# SparkFun_NEO-F9P.net
KiCad netlist of a schematic drawn in EAGLE
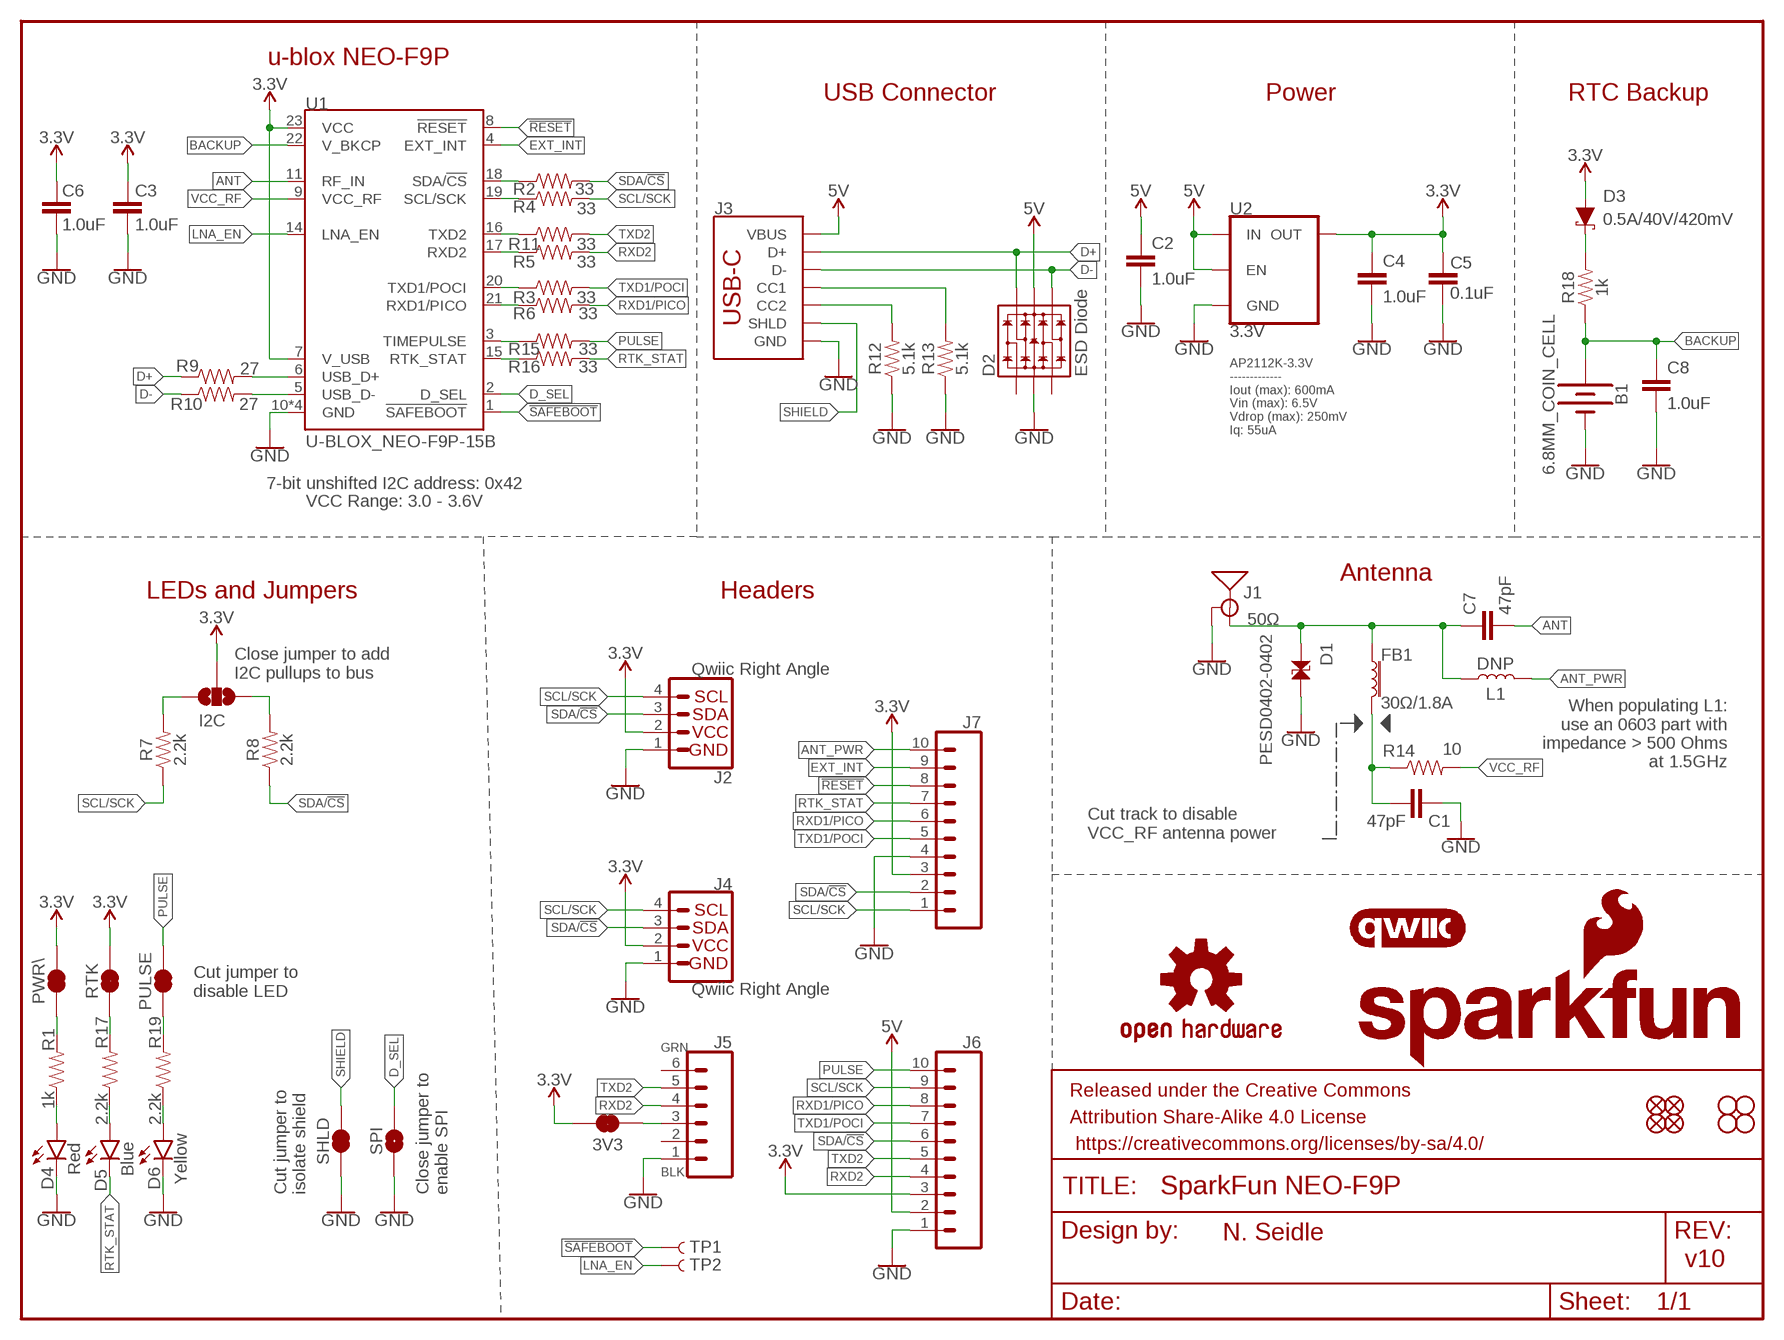
[diagram p0: schematic, sheet 1]

(export (version "E")
  (design (tool "Eeschema 10.0.6"))
  (components
    (comp (ref "3V3")
      (value "JUMPER-SMT_2_NC_TRACE_SILK")
      (footprint "eagle-import:SMT-JUMPER_2_NC_TRACE_SILK")
      (libsource (lib "eagle-import") (part "JUMPER-SMT_2_NC_TRACE_SILK"))
    )
    (comp (ref "B1")
      (value "6.8MM_COIN_CELL")
      (footprint "eagle-import:ML414H_IV01E")
      (libsource (lib "eagle-import") (part "ML414H_IV01E_BATTERY"))
    )
    (comp (ref "C1")
      (value "47pF")
      (footprint "eagle-import:0603")
      (libsource (lib "eagle-import") (part "47PF-0603-50V-5%"))
    )
    (comp (ref "C2")
      (value "1.0uF")
      (footprint "eagle-import:0603")
      (libsource (lib "eagle-import") (part "1.0UF-0603-16V-10%"))
    )
    (comp (ref "C3")
      (value "1.0uF")
      (footprint "eagle-import:0603")
      (libsource (lib "eagle-import") (part "1.0UF-0603-16V-10%"))
    )
    (comp (ref "C4")
      (value "1.0uF")
      (footprint "eagle-import:0603")
      (libsource (lib "eagle-import") (part "1.0UF-0603-16V-10%"))
    )
    (comp (ref "C5")
      (value "0.1uF")
      (footprint "eagle-import:0603")
      (libsource (lib "eagle-import") (part "0.1UF-0603-25V-(+80/-20%)"))
    )
    (comp (ref "C6")
      (value "1.0uF")
      (footprint "eagle-import:0603")
      (libsource (lib "eagle-import") (part "1.0UF-0603-16V-10%"))
    )
    (comp (ref "C7")
      (value "47pF")
      (footprint "eagle-import:0603")
      (libsource (lib "eagle-import") (part "47PF-0603-50V-5%"))
    )
    (comp (ref "C8")
      (value "1.0uF")
      (footprint "eagle-import:0603")
      (libsource (lib "eagle-import") (part "1.0UF-0603-16V-10%-X7R"))
    )
    (comp (ref "D1")
      (value "PESD0402-0402")
      (footprint "eagle-import:0402")
      (fields
        (field (name "DIGIKEY_PART") "PESD0402-140CT-ND")
        (field (name "MOUSE_PART") "650-PESD0402-140")
      )
      (libsource (lib "eagle-import") (part "PESD0402-0402"))
    )
    (comp (ref "D2")
      (value "ESD Diode")
      (footprint "eagle-import:SOT-23-6")
      (libsource (lib "eagle-import") (part "TVS_DIODE_ARRAY_DT1042-04SO-7"))
    )
    (comp (ref "D3")
      (value "0.5A/40V/420mV")
      (footprint "eagle-import:SOD-323")
      (libsource (lib "eagle-import") (part "DIODE-SCHOTTKY-PMEG4005EJ"))
    )
    (comp (ref "D4")
      (value "Red")
      (footprint "eagle-import:LED-0603")
      (libsource (lib "eagle-import") (part "LED-RED0603"))
    )
    (comp (ref "D5")
      (value "Blue")
      (footprint "eagle-import:LED-0603")
      (libsource (lib "eagle-import") (part "LED-BLUE0603"))
    )
    (comp (ref "D6")
      (value "Yellow")
      (footprint "eagle-import:LED-0603")
      (libsource (lib "eagle-import") (part "LED-YELLOW0603"))
    )
    (comp (ref "FB1")
      (value "30Ω/1.8A")
      (footprint "eagle-import:0603")
      (libsource (lib "eagle-import") (part "FERRITE_BEAD-0603"))
    )
    (comp (ref "FRAME1")
      (value "FRAME-LETTER")
      (footprint "eagle-import:CREATIVE_COMMONS")
      (libsource (lib "eagle-import") (part "FRAME-LETTER"))
    )
    (comp (ref "I2C")
      (value "JUMPER-SMT_3_NO_SILK")
      (footprint "eagle-import:SMT-JUMPER_3_NO_SILK")
      (libsource (lib "eagle-import") (part "JUMPER-SMT_3_NO_SILK"))
    )
    (comp (ref "J1")
      (value "ANTENNA-SMA-GROUNDEDEDGE_SMA")
      (footprint "eagle-import:SMA-EDGE")
      (libsource (lib "eagle-import") (part "ANTENNA-SMA-GROUNDEDEDGE_SMA"))
    )
    (comp (ref "J2")
      (value "Qwiic Right Angle")
      (footprint "eagle-import:JST04_1MM_RA")
      (libsource (lib "eagle-import") (part "I2C_STANDARDQWIIC"))
    )
    (comp (ref "J3")
      (value "USB_C_2-LAYER_PADS")
      (footprint "eagle-import:USB-C-16P-2LAYER-PADS")
      (libsource (lib "eagle-import") (part "USB_C_2-LAYER_PADS"))
    )
    (comp (ref "J4")
      (value "Qwiic Right Angle")
      (footprint "eagle-import:JST04_1MM_RA")
      (libsource (lib "eagle-import") (part "I2C_STANDARDQWIIC"))
    )
    (comp (ref "J5")
      (value "CONN_06NO_SILK_FEMALE_PTH")
      (footprint "eagle-import:1X06_NO_SILK")
      (libsource (lib "eagle-import") (part "CONN_06NO_SILK_FEMALE_PTH"))
    )
    (comp (ref "J6")
      (value "CONN_10NO_SILK_PTH_FEMALE")
      (footprint "eagle-import:1X10_NO_SILK")
      (libsource (lib "eagle-import") (part "CONN_10NO_SILK_PTH_FEMALE"))
    )
    (comp (ref "J7")
      (value "CONN_10NO_SILK_PTH_FEMALE")
      (footprint "eagle-import:1X10_NO_SILK")
      (libsource (lib "eagle-import") (part "CONN_10NO_SILK_PTH_FEMALE"))
    )
    (comp (ref "JP21")
      (value "FIDUCIALUFIDUCIAL")
      (footprint "eagle-import:MICRO-FIDUCIAL")
      (libsource (lib "eagle-import") (part "FIDUCIALUFIDUCIAL"))
    )
    (comp (ref "JP31")
      (value "STAND-OFF")
      (footprint "eagle-import:STAND-OFF")
      (libsource (lib "eagle-import") (part "STAND-OFF"))
    )
    (comp (ref "JP41")
      (value "STAND-OFF")
      (footprint "eagle-import:STAND-OFF")
      (libsource (lib "eagle-import") (part "STAND-OFF"))
    )
    (comp (ref "JP61")
      (value "FIDUCIALUFIDUCIAL")
      (footprint "eagle-import:MICRO-FIDUCIAL")
      (libsource (lib "eagle-import") (part "FIDUCIALUFIDUCIAL"))
    )
    (comp (ref "JP71")
      (value "FIDUCIALUFIDUCIAL")
      (footprint "eagle-import:MICRO-FIDUCIAL")
      (libsource (lib "eagle-import") (part "FIDUCIALUFIDUCIAL"))
    )
    (comp (ref "JP81")
      (value "FIDUCIALUFIDUCIAL")
      (footprint "eagle-import:MICRO-FIDUCIAL")
      (libsource (lib "eagle-import") (part "FIDUCIALUFIDUCIAL"))
    )
    (comp (ref "JP91")
      (value "STAND-OFF")
      (footprint "eagle-import:STAND-OFF")
      (libsource (lib "eagle-import") (part "STAND-OFF"))
    )
    (comp (ref "JP101")
      (value "STAND-OFF")
      (footprint "eagle-import:STAND-OFF")
      (libsource (lib "eagle-import") (part "STAND-OFF"))
    )
    (comp (ref "L1")
      (value "DNP")
      (footprint "eagle-import:0603_NO-CREAM")
      (libsource (lib "eagle-import") (part "DNP-0603_NO-CREAM"))
    )
    (comp (ref "LOGO2")
      (value "SFE_LOGO_NAME_FLAME.1_INCH")
      (footprint "eagle-import:SFE_LOGO_NAME_FLAME_.1")
      (libsource (lib "eagle-import") (part "SFE_LOGO_NAME_FLAME.1_INCH"))
    )
    (comp (ref "LOGO3")
      (value "SFE_LOGO_NAME_FLAME7_MM")
      (footprint "eagle-import:SFE_LOGO_NAME_FLAME_7MM")
      (libsource (lib "eagle-import") (part "SFE_LOGO_NAME_FLAME7_MM"))
    )
    (comp (ref "LOGO4")
      (value "OSHW-LOGOS")
      (footprint "eagle-import:OSHW-LOGO-S")
      (libsource (lib "eagle-import") (part "OSHW-LOGOS"))
    )
    (comp (ref "LOGO5")
      (value "QWIIC_LOGO_5MM")
      (footprint "eagle-import:QWIIC_5MM")
      (libsource (lib "eagle-import") (part "QWIIC_LOGO_5MM"))
    )
    (comp (ref "PULSE")
      (value "JUMPER-SMT_2_NC_TRACE_SILK")
      (footprint "eagle-import:SMT-JUMPER_2_NC_TRACE_SILK")
      (libsource (lib "eagle-import") (part "JUMPER-SMT_2_NC_TRACE_SILK"))
    )
    (comp (ref "PWR\\")
      (value "JUMPER-SMT_2_NC_TRACE_SILK")
      (footprint "eagle-import:SMT-JUMPER_2_NC_TRACE_SILK")
      (libsource (lib "eagle-import") (part "JUMPER-SMT_2_NC_TRACE_SILK"))
    )
    (comp (ref "R1")
      (value "1k")
      (footprint "eagle-import:0603")
      (libsource (lib "eagle-import") (part "1KOHM-0603-1/10W-1%"))
    )
    (comp (ref "R2")
      (value "33")
      (footprint "eagle-import:0603")
      (libsource (lib "eagle-import") (part "33OHM-0603-1/10W-1%"))
    )
    (comp (ref "R3")
      (value "33")
      (footprint "eagle-import:0603")
      (libsource (lib "eagle-import") (part "33OHM-0603-1/10W-1%"))
    )
    (comp (ref "R4")
      (value "33")
      (footprint "eagle-import:0603")
      (libsource (lib "eagle-import") (part "33OHM-0603-1/10W-1%"))
    )
    (comp (ref "R5")
      (value "33")
      (footprint "eagle-import:0603")
      (libsource (lib "eagle-import") (part "33OHM-0603-1/10W-1%"))
    )
    (comp (ref "R6")
      (value "33")
      (footprint "eagle-import:0603")
      (libsource (lib "eagle-import") (part "33OHM-0603-1/10W-1%"))
    )
    (comp (ref "R7")
      (value "2.2k")
      (footprint "eagle-import:0603")
      (libsource (lib "eagle-import") (part "2.2KOHM-0603-1/10W-1%"))
    )
    (comp (ref "R8")
      (value "2.2k")
      (footprint "eagle-import:0603")
      (libsource (lib "eagle-import") (part "2.2KOHM-0603-1/10W-1%"))
    )
    (comp (ref "R9")
      (value "27")
      (footprint "eagle-import:0603")
      (libsource (lib "eagle-import") (part "27OHM-0603-1/10W-1%"))
    )
    (comp (ref "R10")
      (value "27")
      (footprint "eagle-import:0603")
      (libsource (lib "eagle-import") (part "27OHM-0603-1/10W-1%"))
    )
    (comp (ref "R11")
      (value "33")
      (footprint "eagle-import:0603")
      (libsource (lib "eagle-import") (part "33OHM-0603-1/10W-1%"))
    )
    (comp (ref "R12")
      (value "5.1k")
      (footprint "eagle-import:0603")
      (libsource (lib "eagle-import") (part "5.1KOHM5.1KOHM-0603-1/10W-1%"))
    )
    (comp (ref "R13")
      (value "5.1k")
      (footprint "eagle-import:0603")
      (libsource (lib "eagle-import") (part "5.1KOHM5.1KOHM-0603-1/10W-1%"))
    )
    (comp (ref "R14")
      (value "10")
      (footprint "eagle-import:0603")
      (libsource (lib "eagle-import") (part "10OHM-0603-1/10W-1%"))
    )
    (comp (ref "R15")
      (value "33")
      (footprint "eagle-import:0603")
      (libsource (lib "eagle-import") (part "33OHM-0603-1/10W-1%"))
    )
    (comp (ref "R16")
      (value "33")
      (footprint "eagle-import:0603")
      (libsource (lib "eagle-import") (part "33OHM-0603-1/10W-1%"))
    )
    (comp (ref "R17")
      (value "2.2k")
      (footprint "eagle-import:0603")
      (libsource (lib "eagle-import") (part "2.2KOHM-0603-1/10W-1%"))
    )
    (comp (ref "R18")
      (value "1k")
      (footprint "eagle-import:0603")
      (libsource (lib "eagle-import") (part "1KOHM-0603-1/10W-1%"))
    )
    (comp (ref "R19")
      (value "2.2k")
      (footprint "eagle-import:0603")
      (libsource (lib "eagle-import") (part "2.2KOHM-0603-1/10W-1%"))
    )
    (comp (ref "RTK")
      (value "JUMPER-SMT_2_NC_TRACE_SILK")
      (footprint "eagle-import:SMT-JUMPER_2_NC_TRACE_SILK")
      (libsource (lib "eagle-import") (part "JUMPER-SMT_2_NC_TRACE_SILK"))
    )
    (comp (ref "SHLD")
      (value "JUMPER-SMT_2_NC_TRACE_SILK")
      (footprint "eagle-import:SMT-JUMPER_2_NC_TRACE_SILK")
      (libsource (lib "eagle-import") (part "JUMPER-SMT_2_NC_TRACE_SILK"))
    )
    (comp (ref "SPI")
      (value "JUMPER-SMT_2_NO_SILK")
      (footprint "eagle-import:SMT-JUMPER_2_NO_SILK")
      (libsource (lib "eagle-import") (part "JUMPER-SMT_2_NO_SILK"))
    )
    (comp (ref "TP1")
      (value "TEST-POINTPOGO_PTH")
      (footprint "eagle-import:1X01_NO_SILK")
      (libsource (lib "eagle-import") (part "TEST-POINTPOGO_PTH"))
    )
    (comp (ref "TP2")
      (value "TEST-POINTPOGO_PTH")
      (footprint "eagle-import:1X01_NO_SILK")
      (libsource (lib "eagle-import") (part "TEST-POINTPOGO_PTH"))
    )
    (comp (ref "U1")
      (value "U-BLOX_NEO-F9P-15B")
      (footprint "eagle-import:NEO-M9N_M8T_M8U_D9S_F9P")
      (libsource (lib "eagle-import") (part "U-BLOX_NEO-F9P-15B"))
    )
    (comp (ref "U2")
      (value "3.3V")
      (footprint "eagle-import:SOT23-5")
      (libsource (lib "eagle-import") (part "V_REG_AP2112K-3.3V"))
    )
  )
  (nets
    (net (code "1") (name "/SDA{slash}~{CS}") (class "Default")
      (node (ref "J2") (pin "3") (pinfunction "3_3") (pintype "passive"))
      (node (ref "J4") (pin "3") (pinfunction "3_3") (pintype "passive"))
      (node (ref "J6") (pin "6") (pinfunction "6_6") (pintype "passive"))
      (node (ref "J7") (pin "2") (pinfunction "2_2") (pintype "passive"))
      (node (ref "R2") (pin "2") (pinfunction "2_2") (pintype "passive"))
      (node (ref "R8") (pin "1") (pinfunction "1_1") (pintype "passive"))
    )
    (net (code "2") (name "/~{RESET}") (class "Default")
      (node (ref "J7") (pin "8") (pinfunction "8_8") (pintype "passive"))
      (node (ref "U1") (pin "8") (pinfunction "~{RESET}_8") (pintype "input"))
    )
    (net (code "3") (name "/~{SAFEBOOT}") (class "Default")
      (node (ref "TP1") (pin "1") (pinfunction "1_1") (pintype "bidirectional"))
      (node (ref "U1") (pin "1") (pinfunction "~{SAFEBOOT}_1") (pintype "input"))
    )
    (net (code "4") (name "3.3V") (class "Default")
      (node (ref "3V3") (pin "2") (pinfunction "2_2") (pintype "passive"))
      (node (ref "C3") (pin "1") (pinfunction "1_1") (pintype "passive"))
      (node (ref "C4") (pin "1") (pinfunction "1_1") (pintype "passive"))
      (node (ref "C5") (pin "2") (pinfunction "2_2") (pintype "passive"))
      (node (ref "C6") (pin "1") (pinfunction "1_1") (pintype "passive"))
      (node (ref "D3") (pin "A") (pinfunction "A_A") (pintype "passive"))
      (node (ref "I2C") (pin "2") (pinfunction "2_2") (pintype "passive"))
      (node (ref "J2") (pin "2") (pinfunction "2_2") (pintype "power_in"))
      (node (ref "J4") (pin "2") (pinfunction "2_2") (pintype "power_in"))
      (node (ref "J6") (pin "3") (pinfunction "3_3") (pintype "passive"))
      (node (ref "J7") (pin "3") (pinfunction "3_3") (pintype "passive"))
      (node (ref "PWR\\") (pin "2") (pinfunction "2_2") (pintype "passive"))
      (node (ref "RTK") (pin "2") (pinfunction "2_2") (pintype "passive"))
      (node (ref "U1") (pin "23") (pinfunction "VCC_23") (pintype "power_in"))
      (node (ref "U1") (pin "7") (pinfunction "V_USB_7") (pintype "power_in"))
      (node (ref "U2") (pin "5") (pinfunction "OUT_5") (pintype "passive"))
    )
    (net (code "5") (name "5V") (class "Default")
      (node (ref "C2") (pin "1") (pinfunction "1_1") (pintype "passive"))
      (node (ref "D2") (pin "5") (pinfunction "VCC_5") (pintype "bidirectional"))
      (node (ref "J3") (pin "VBUS1") (pinfunction "VBUS_VBUS1") (pintype "bidirectional"))
      (node (ref "J3") (pin "VBUS2") (pinfunction "VBUS_VBUS2") (pintype "bidirectional"))
      (node (ref "J6") (pin "2") (pinfunction "2_2") (pintype "passive"))
      (node (ref "U2") (pin "1") (pinfunction "IN_1") (pintype "input"))
      (node (ref "U2") (pin "3") (pinfunction "EN_3") (pintype "input"))
    )
    (net (code "6") (name "ANT") (class "Default")
      (node (ref "C7") (pin "2") (pinfunction "2_2") (pintype "passive"))
      (node (ref "U1") (pin "11") (pinfunction "RF_IN_11") (pintype "input"))
    )
    (net (code "7") (name "ANT_PWR") (class "Default")
      (node (ref "J7") (pin "10") (pinfunction "10_10") (pintype "passive"))
      (node (ref "L1") (pin "2") (pinfunction "2_2") (pintype "passive"))
    )
    (net (code "8") (name "BACKUP") (class "Default")
      (node (ref "B1") (pin "+") (pinfunction "+_+") (pintype "power_in"))
      (node (ref "C8") (pin "1") (pinfunction "1_1") (pintype "passive"))
      (node (ref "R18") (pin "1") (pinfunction "1_1") (pintype "passive"))
      (node (ref "U1") (pin "22") (pinfunction "V_BKCP_22") (pintype "power_in"))
    )
    (net (code "9") (name "D+") (class "Default")
      (node (ref "D2") (pin "6") (pinfunction "IO4_6") (pintype "bidirectional"))
      (node (ref "J3") (pin "A6") (pinfunction "D+_A6") (pintype "bidirectional"))
      (node (ref "J3") (pin "B6") (pinfunction "D+_B6") (pintype "bidirectional"))
      (node (ref "R9") (pin "1") (pinfunction "1_1") (pintype "passive"))
    )
    (net (code "10") (name "D-") (class "Default")
      (node (ref "D2") (pin "4") (pinfunction "IO3_4") (pintype "bidirectional"))
      (node (ref "J3") (pin "A7") (pinfunction "D-_A7") (pintype "bidirectional"))
      (node (ref "J3") (pin "B7") (pinfunction "D-_B7") (pintype "bidirectional"))
      (node (ref "R10") (pin "1") (pinfunction "1_1") (pintype "passive"))
    )
    (net (code "11") (name "D_SEL") (class "Default")
      (node (ref "SPI") (pin "2") (pinfunction "2_2") (pintype "passive"))
      (node (ref "U1") (pin "2") (pinfunction "D_SEL_2") (pintype "input"))
    )
    (net (code "12") (name "EXT_INT") (class "Default")
      (node (ref "J7") (pin "9") (pinfunction "9_9") (pintype "passive"))
      (node (ref "U1") (pin "4") (pinfunction "EXT_INT_4") (pintype "input"))
    )
    (net (code "13") (name "GND") (class "Default")
      (node (ref "B1") (pin "-") (pinfunction "-_-") (pintype "power_in"))
      (node (ref "C1") (pin "2") (pinfunction "2_2") (pintype "passive"))
      (node (ref "C2") (pin "2") (pinfunction "2_2") (pintype "passive"))
      (node (ref "C3") (pin "2") (pinfunction "2_2") (pintype "passive"))
      (node (ref "C4") (pin "2") (pinfunction "2_2") (pintype "passive"))
      (node (ref "C5") (pin "1") (pinfunction "1_1") (pintype "passive"))
      (node (ref "C6") (pin "2") (pinfunction "2_2") (pintype "passive"))
      (node (ref "C8") (pin "2") (pinfunction "2_2") (pintype "passive"))
      (node (ref "D1") (pin "2") (pinfunction "2_2") (pintype "bidirectional"))
      (node (ref "D2") (pin "2") (pinfunction "VSS_2") (pintype "bidirectional"))
      (node (ref "D4") (pin "C") (pinfunction "C_C") (pintype "passive"))
      (node (ref "D6") (pin "C") (pinfunction "C_C") (pintype "passive"))
      (node (ref "J1") (pin "GND@0") (pinfunction "GND_GND@0") (pintype "bidirectional"))
      (node (ref "J1") (pin "GND@1") (pinfunction "GND_GND@1") (pintype "bidirectional"))
      (node (ref "J1") (pin "GND@2") (pinfunction "GND_GND@2") (pintype "bidirectional"))
      (node (ref "J1") (pin "GND@3") (pinfunction "GND_GND@3") (pintype "bidirectional"))
      (node (ref "J2") (pin "1") (pinfunction "1_1") (pintype "power_in"))
      (node (ref "J3") (pin "GND") (pinfunction "GND_GND") (pintype "bidirectional"))
      (node (ref "J3") (pin "GND2") (pinfunction "GND_GND2") (pintype "bidirectional"))
      (node (ref "J4") (pin "1") (pinfunction "1_1") (pintype "power_in"))
      (node (ref "J5") (pin "1") (pinfunction "1_1") (pintype "passive"))
      (node (ref "J6") (pin "1") (pinfunction "1_1") (pintype "passive"))
      (node (ref "J7") (pin "4") (pinfunction "4_4") (pintype "passive"))
      (node (ref "R12") (pin "1") (pinfunction "1_1") (pintype "passive"))
      (node (ref "R13") (pin "1") (pinfunction "1_1") (pintype "passive"))
      (node (ref "SHLD") (pin "1") (pinfunction "1_1") (pintype "passive"))
      (node (ref "SPI") (pin "1") (pinfunction "1_1") (pintype "passive"))
      (node (ref "U1") (pin "10") (pinfunction "GND_10") (pintype "power_in"))
      (node (ref "U1") (pin "12") (pinfunction "GND_12") (pintype "power_in"))
      (node (ref "U1") (pin "13") (pinfunction "GND_13") (pintype "power_in"))
      (node (ref "U1") (pin "24") (pinfunction "GND_24") (pintype "power_in"))
      (node (ref "U2") (pin "2") (pinfunction "GND_2") (pintype "input"))
    )
    (net (code "14") (name "LNA_EN") (class "Default")
      (node (ref "TP2") (pin "1") (pinfunction "1_1") (pintype "bidirectional"))
      (node (ref "U1") (pin "14") (pinfunction "LNA_EN_14") (pintype "output"))
    )
    (net (code "15") (name "Net-(3V3-Pad1)") (class "Default")
      (node (ref "3V3") (pin "1") (pinfunction "1_1") (pintype "passive"))
      (node (ref "J5") (pin "3") (pinfunction "3_3") (pintype "passive"))
    )
    (net (code "16") (name "Net-(C1-Pad1)") (class "Default")
      (node (ref "C1") (pin "1") (pinfunction "1_1") (pintype "passive"))
      (node (ref "FB1") (pin "2") (pinfunction "2_2") (pintype "passive"))
      (node (ref "R14") (pin "1") (pinfunction "1_1") (pintype "passive"))
    )
    (net (code "17") (name "Net-(D3-PadC)") (class "Default")
      (node (ref "D3") (pin "C") (pinfunction "C_C") (pintype "passive"))
      (node (ref "R18") (pin "2") (pinfunction "2_2") (pintype "passive"))
    )
    (net (code "18") (name "Net-(D4-PadA)") (class "Default")
      (node (ref "D4") (pin "A") (pinfunction "A_A") (pintype "passive"))
      (node (ref "R1") (pin "1") (pinfunction "1_1") (pintype "passive"))
    )
    (net (code "19") (name "Net-(D5-PadA)") (class "Default")
      (node (ref "D5") (pin "A") (pinfunction "A_A") (pintype "passive"))
      (node (ref "R17") (pin "1") (pinfunction "1_1") (pintype "passive"))
    )
    (net (code "20") (name "Net-(D6-PadA)") (class "Default")
      (node (ref "D6") (pin "A") (pinfunction "A_A") (pintype "passive"))
      (node (ref "R19") (pin "1") (pinfunction "1_1") (pintype "passive"))
    )
    (net (code "21") (name "Net-(I2C-Pad1)") (class "Default")
      (node (ref "I2C") (pin "1") (pinfunction "1_1") (pintype "passive"))
      (node (ref "R8") (pin "2") (pinfunction "2_2") (pintype "passive"))
    )
    (net (code "22") (name "Net-(I2C-Pad3)") (class "Default")
      (node (ref "I2C") (pin "3") (pinfunction "3_3") (pintype "passive"))
      (node (ref "R7") (pin "2") (pinfunction "2_2") (pintype "passive"))
    )
    (net (code "23") (name "Net-(J1-SIGNAL)") (class "Default")
      (node (ref "C7") (pin "1") (pinfunction "1_1") (pintype "passive"))
      (node (ref "D1") (pin "1") (pinfunction "1_1") (pintype "bidirectional"))
      (node (ref "FB1") (pin "1") (pinfunction "1_1") (pintype "passive"))
      (node (ref "J1") (pin "SIG") (pinfunction "SIGNAL_SIG") (pintype "bidirectional"))
      (node (ref "L1") (pin "1") (pinfunction "1_1") (pintype "passive"))
    )
    (net (code "24") (name "Net-(J3-CC1)") (class "Default")
      (node (ref "J3") (pin "A5") (pinfunction "CC1_A5") (pintype "bidirectional"))
      (node (ref "R13") (pin "2") (pinfunction "2_2") (pintype "passive"))
    )
    (net (code "25") (name "Net-(J3-CC2)") (class "Default")
      (node (ref "J3") (pin "B5") (pinfunction "CC2_B5") (pintype "bidirectional"))
      (node (ref "R12") (pin "2") (pinfunction "2_2") (pintype "passive"))
    )
    (net (code "26") (name "Net-(PULSE-Pad1)") (class "Default")
      (node (ref "PULSE") (pin "1") (pinfunction "1_1") (pintype "passive"))
      (node (ref "R19") (pin "2") (pinfunction "2_2") (pintype "passive"))
    )
    (net (code "27") (name "Net-(PWR\\-Pad1)") (class "Default")
      (node (ref "PWR\\") (pin "1") (pinfunction "1_1") (pintype "passive"))
      (node (ref "R1") (pin "2") (pinfunction "2_2") (pintype "passive"))
    )
    (net (code "28") (name "Net-(R17-Pad2)") (class "Default")
      (node (ref "R17") (pin "2") (pinfunction "2_2") (pintype "passive"))
      (node (ref "RTK") (pin "1") (pinfunction "1_1") (pintype "passive"))
    )
    (net (code "29") (name "Net-(U1-RTK_STAT)") (class "Default")
      (node (ref "R16") (pin "1") (pinfunction "1_1") (pintype "passive"))
      (node (ref "U1") (pin "15") (pinfunction "RTK_STAT_15") (pintype "input"))
    )
    (net (code "30") (name "Net-(U1-RXD1{slash}PICO)") (class "Default")
      (node (ref "R6") (pin "1") (pinfunction "1_1") (pintype "passive"))
      (node (ref "U1") (pin "21") (pinfunction "RXD1/PICO_21") (pintype "input"))
    )
    (net (code "31") (name "Net-(U1-RXD2)") (class "Default")
      (node (ref "R5") (pin "1") (pinfunction "1_1") (pintype "passive"))
      (node (ref "U1") (pin "17") (pinfunction "RXD2_17") (pintype "input"))
    )
    (net (code "32") (name "Net-(U1-SCL{slash}SCK)") (class "Default")
      (node (ref "R4") (pin "1") (pinfunction "1_1") (pintype "passive"))
      (node (ref "U1") (pin "19") (pinfunction "SCL/SCK_19") (pintype "bidirectional"))
    )
    (net (code "33") (name "Net-(U1-SDA{slash}~{CS})") (class "Default")
      (node (ref "R2") (pin "1") (pinfunction "1_1") (pintype "passive"))
      (node (ref "U1") (pin "18") (pinfunction "SDA/~{CS}_18") (pintype "bidirectional"))
    )
    (net (code "34") (name "Net-(U1-TIMEPULSE)") (class "Default")
      (node (ref "R15") (pin "1") (pinfunction "1_1") (pintype "passive"))
      (node (ref "U1") (pin "3") (pinfunction "TIMEPULSE_3") (pintype "output"))
    )
    (net (code "35") (name "Net-(U1-TXD1{slash}POCI)") (class "Default")
      (node (ref "R3") (pin "1") (pinfunction "1_1") (pintype "passive"))
      (node (ref "U1") (pin "20") (pinfunction "TXD1/POCI_20") (pintype "output"))
    )
    (net (code "36") (name "Net-(U1-TXD2)") (class "Default")
      (node (ref "R11") (pin "1") (pinfunction "1_1") (pintype "passive"))
      (node (ref "U1") (pin "16") (pinfunction "TXD2_16") (pintype "output"))
    )
    (net (code "37") (name "Net-(U1-USB_D+)") (class "Default")
      (node (ref "R9") (pin "2") (pinfunction "2_2") (pintype "passive"))
      (node (ref "U1") (pin "6") (pinfunction "USB_D+_6") (pintype "bidirectional"))
    )
    (net (code "38") (name "Net-(U1-USB_D-)") (class "Default")
      (node (ref "R10") (pin "2") (pinfunction "2_2") (pintype "passive"))
      (node (ref "U1") (pin "5") (pinfunction "USB_D-_5") (pintype "bidirectional"))
    )
    (net (code "39") (name "PULSE") (class "Default")
      (node (ref "J6") (pin "10") (pinfunction "10_10") (pintype "passive"))
      (node (ref "PULSE") (pin "2") (pinfunction "2_2") (pintype "passive"))
      (node (ref "R15") (pin "2") (pinfunction "2_2") (pintype "passive"))
    )
    (net (code "40") (name "RTK_STAT") (class "Default")
      (node (ref "D5") (pin "C") (pinfunction "C_C") (pintype "passive"))
      (node (ref "J7") (pin "7") (pinfunction "7_7") (pintype "passive"))
      (node (ref "R16") (pin "2") (pinfunction "2_2") (pintype "passive"))
    )
    (net (code "41") (name "RXD1{slash}PICO") (class "Default")
      (node (ref "J6") (pin "8") (pinfunction "8_8") (pintype "passive"))
      (node (ref "J7") (pin "6") (pinfunction "6_6") (pintype "passive"))
      (node (ref "R6") (pin "2") (pinfunction "2_2") (pintype "passive"))
    )
    (net (code "42") (name "RXD2") (class "Default")
      (node (ref "J5") (pin "4") (pinfunction "4_4") (pintype "passive"))
      (node (ref "J6") (pin "4") (pinfunction "4_4") (pintype "passive"))
      (node (ref "R5") (pin "2") (pinfunction "2_2") (pintype "passive"))
    )
    (net (code "43") (name "SCL{slash}SCK") (class "Default")
      (node (ref "J2") (pin "4") (pinfunction "4_4") (pintype "passive"))
      (node (ref "J4") (pin "4") (pinfunction "4_4") (pintype "passive"))
      (node (ref "J6") (pin "9") (pinfunction "9_9") (pintype "passive"))
      (node (ref "J7") (pin "1") (pinfunction "1_1") (pintype "passive"))
      (node (ref "R4") (pin "2") (pinfunction "2_2") (pintype "passive"))
      (node (ref "R7") (pin "1") (pinfunction "1_1") (pintype "passive"))
    )
    (net (code "44") (name "SHIELD") (class "Default")
      (node (ref "J3") (pin "SHLD1") (pinfunction "SHLD_SHLD1") (pintype "bidirectional"))
      (node (ref "J3") (pin "SHLD2") (pinfunction "SHLD_SHLD2") (pintype "bidirectional"))
      (node (ref "J3") (pin "SHLD3") (pinfunction "SHLD_SHLD3") (pintype "bidirectional"))
      (node (ref "J3") (pin "SHLD4") (pinfunction "SHLD_SHLD4") (pintype "bidirectional"))
      (node (ref "SHLD") (pin "2") (pinfunction "2_2") (pintype "passive"))
    )
    (net (code "45") (name "TXD1{slash}POCI") (class "Default")
      (node (ref "J6") (pin "7") (pinfunction "7_7") (pintype "passive"))
      (node (ref "J7") (pin "5") (pinfunction "5_5") (pintype "passive"))
      (node (ref "R3") (pin "2") (pinfunction "2_2") (pintype "passive"))
    )
    (net (code "46") (name "TXD2") (class "Default")
      (node (ref "J5") (pin "5") (pinfunction "5_5") (pintype "passive"))
      (node (ref "J6") (pin "5") (pinfunction "5_5") (pintype "passive"))
      (node (ref "R11") (pin "2") (pinfunction "2_2") (pintype "passive"))
    )
    (net (code "47") (name "VCC_RF") (class "Default")
      (node (ref "R14") (pin "2") (pinfunction "2_2") (pintype "passive"))
      (node (ref "U1") (pin "9") (pinfunction "VCC_RF_9") (pintype "output"))
    )
    (net (code "48") (name "unconnected-(D2-IO1-Pad1)") (class "Default")
      (node (ref "D2") (pin "1") (pinfunction "IO1_1") (pintype "bidirectional"))
    )
    (net (code "49") (name "unconnected-(D2-IO2-Pad3)") (class "Default")
      (node (ref "D2") (pin "3") (pinfunction "IO2_3") (pintype "bidirectional"))
    )
    (net (code "50") (name "unconnected-(J5-Pad2)") (class "Default")
      (node (ref "J5") (pin "2") (pinfunction "2_2") (pintype "passive"))
    )
    (net (code "51") (name "unconnected-(J5-Pad6)") (class "Default")
      (node (ref "J5") (pin "6") (pinfunction "6_6") (pintype "passive"))
    )
  )
)
